# ESP8266.net
KiCad netlist of a schematic drawn in Altium Designer
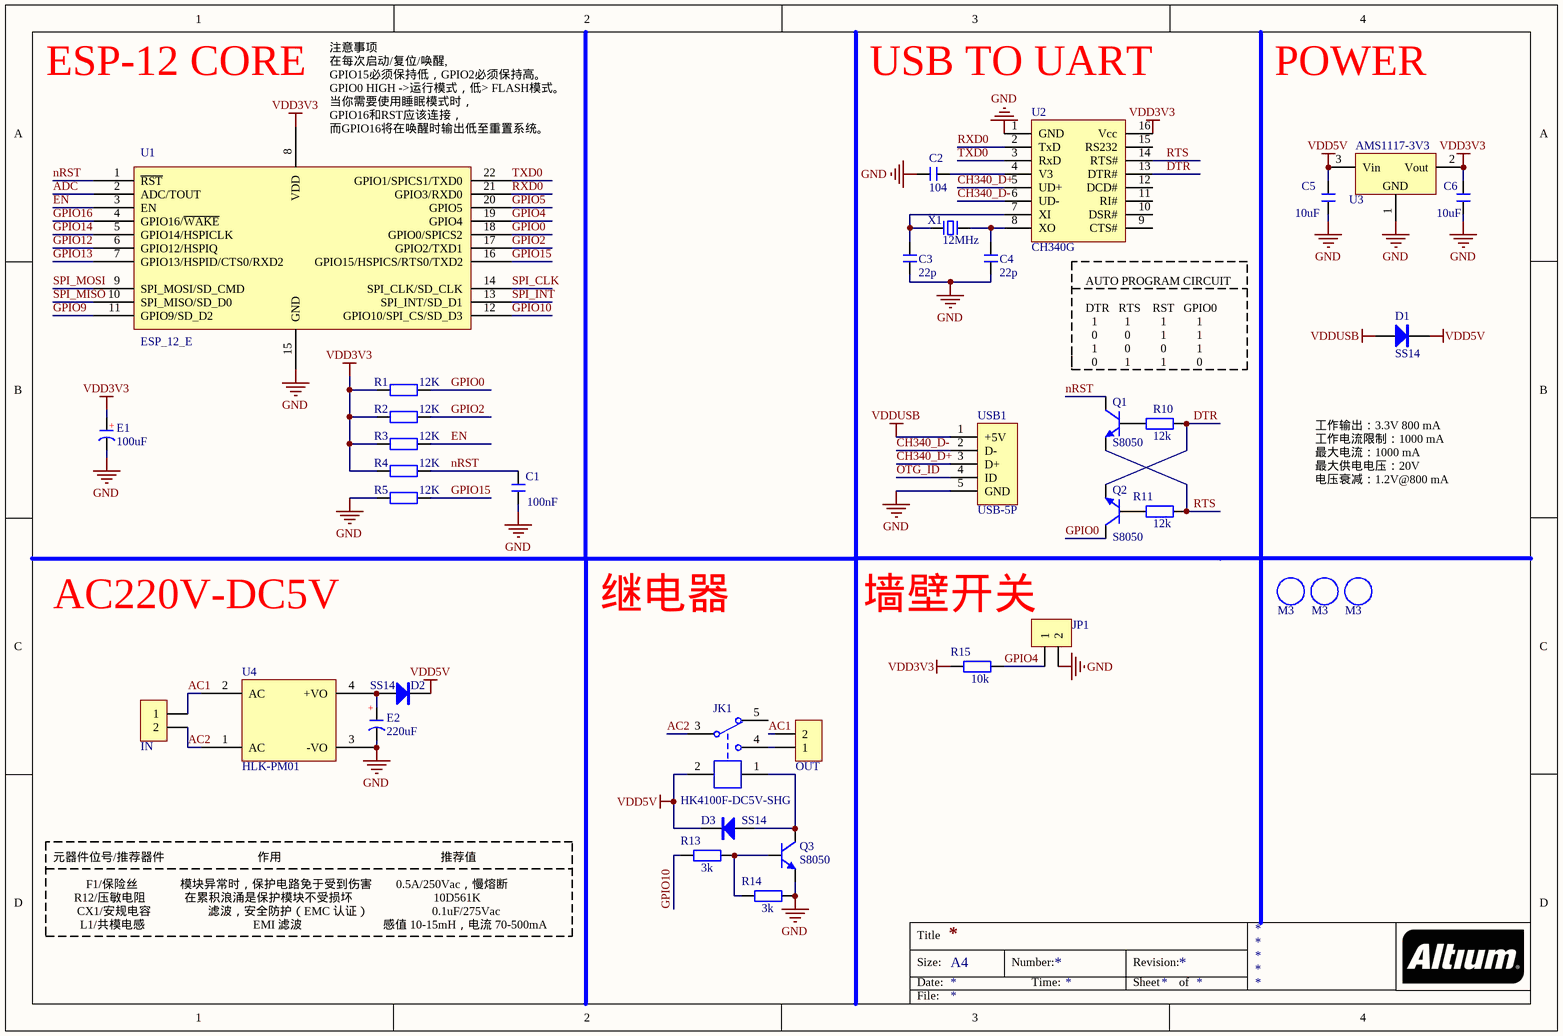
[diagram p0: ESP8266控制器.SchDoc]

(export (version "E")
  (design (tool "Eeschema 10.0.6"))
  (components
    (comp (ref "1")
      (value "M3")
      (footprint "M3 125X200")
      (description "铜柱孔")
      (fields (field (name "版权归属") "源创客"))
      (libsource (lib "海龍集成库") (part "M3"))
    )
    (comp (ref "2")
      (value "M3")
      (footprint "M3 125X200")
      (description "铜柱孔")
      (fields (field (name "版权归属") "源创客"))
      (libsource (lib "海龍集成库") (part "M3"))
    )
    (comp (ref "3")
      (value "M3")
      (footprint "M3 125X200")
      (description "铜柱孔")
      (fields (field (name "版权归属") "源创客"))
      (libsource (lib "海龍集成库") (part "M3"))
    )
    (comp (ref "C1")
      (value "100nF")
      (footprint "C 0603_M")
      (description "无极性贴片电容")
      (fields (field (name "版权归属") "源创客"))
      (libsource (lib "海龍集成库") (part "C"))
    )
    (comp (ref "C2")
      (value "104")
      (footprint "C 0603_M")
      (description "无极性贴片电容")
      (fields (field (name "版权归属") "源创客"))
      (libsource (lib "海龍集成库") (part "C"))
    )
    (comp (ref "C3")
      (value "22p")
      (footprint "C 0603_M")
      (description "无极性贴片电容")
      (fields (field (name "版权归属") "源创客"))
      (libsource (lib "海龍集成库") (part "C"))
    )
    (comp (ref "C4")
      (value "22p")
      (footprint "C 0603_M")
      (description "无极性贴片电容")
      (fields (field (name "版权归属") "源创客"))
      (libsource (lib "海龍集成库") (part "C"))
    )
    (comp (ref "C5")
      (value "10uF")
      (footprint "C 0603_M")
      (description "无极性贴片电容")
      (fields (field (name "版权归属") "源创客"))
      (libsource (lib "海龍集成库") (part "C"))
    )
    (comp (ref "C6")
      (value "10uF")
      (footprint "C 0603_M")
      (description "无极性贴片电容")
      (fields (field (name "版权归属") "源创客"))
      (libsource (lib "海龍集成库") (part "C"))
    )
    (comp (ref "D1")
      (value "SS14")
      (footprint "SMA")
      (description "肖特基二极管")
      (fields (field (name "版权归属") "源创客"))
      (libsource (lib "海龍集成库") (part "SS14"))
    )
    (comp (ref "D2")
      (value "SS14")
      (footprint "SMA")
      (description "肖特基二极管")
      (fields (field (name "版权归属") "源创客"))
      (libsource (lib "海龍集成库") (part "SS14"))
    )
    (comp (ref "D3")
      (value "SS14")
      (footprint "SMA")
      (description "肖特基二极管")
      (fields (field (name "版权归属") "源创客"))
      (libsource (lib "海龍集成库") (part "SS14"))
    )
    (comp (ref "E1")
      (value "100uF")
      (footprint "CD D(7343)")
      (description "贴片钽电容")
      (fields (field (name "版权归属") "源创客"))
      (libsource (lib "海龍集成库") (part "C-CD"))
    )
    (comp (ref "E2")
      (value "220uF")
      (footprint "CD D(7343)")
      (description "贴片钽电容")
      (fields (field (name "版权归属") "源创客"))
      (libsource (lib "") (part "C-CD_1"))
    )
    (comp (ref "IN")
      (value "HDR-1X2")
      (footprint "KF301-5.0-2P")
      (description "2P接插件")
      (fields (field (name "版权归属") "源创客"))
      (libsource (lib "") (part "Header 2 5.0_1"))
    )
    (comp (ref "JK1")
      (value "HK4100F-DC5V-SHG")
      (footprint "HK4100F")
      (description "一组转换")
      (fields (field (name "版权归属") "源创客"))
      (libsource (lib "海龍集成库") (part "HK4100F"))
    )
    (comp (ref "JP1")
      (value "HDR-1X2")
      (footprint "KF350-2P")
      (description "2P接插件")
      (fields (field (name "版权归属") "源创客"))
      (libsource (lib "海龍集成库") (part "Header 2 3.5"))
    )
    (comp (ref "OUT")
      (value "HDR-1X2")
      (footprint "KF301-5.0-2P")
      (description "2P接插件")
      (fields (field (name "版权归属") "源创客"))
      (libsource (lib "海龍集成库") (part "Header 2 5.0"))
    )
    (comp (ref "Q1")
      (value "S8050")
      (footprint "SOT23-3N")
      (description "高频放大-NPN型")
      (fields (field (name "版权归属") "源创客"))
      (libsource (lib "海龍集成库") (part "8050-SMD"))
    )
    (comp (ref "Q2")
      (value "S8050")
      (footprint "SOT23-3N")
      (description "高频放大-NPN型")
      (fields (field (name "版权归属") "源创客"))
      (libsource (lib "海龍集成库") (part "8050-SMD"))
    )
    (comp (ref "Q3")
      (value "S8050")
      (footprint "SOT23-3N")
      (description "高频放大-NPN型")
      (fields (field (name "版权归属") "源创客"))
      (libsource (lib "海龍集成库") (part "8050-SMD"))
    )
    (comp (ref "R1")
      (value "12K")
      (footprint "R 0603_M")
      (description "贴片电阻")
      (fields (field (name "版权归属") "源创客"))
      (libsource (lib "海龍集成库") (part "R"))
    )
    (comp (ref "R2")
      (value "12K")
      (footprint "R 0603_M")
      (description "贴片电阻")
      (fields (field (name "版权归属") "源创客"))
      (libsource (lib "海龍集成库") (part "R"))
    )
    (comp (ref "R3")
      (value "12K")
      (footprint "R 0603_M")
      (description "贴片电阻")
      (fields (field (name "版权归属") "源创客"))
      (libsource (lib "海龍集成库") (part "R"))
    )
    (comp (ref "R4")
      (value "12K")
      (footprint "R 0603_M")
      (description "贴片电阻")
      (fields (field (name "版权归属") "源创客"))
      (libsource (lib "海龍集成库") (part "R"))
    )
    (comp (ref "R5")
      (value "12K")
      (footprint "R 0603_M")
      (description "贴片电阻")
      (fields (field (name "版权归属") "源创客"))
      (libsource (lib "海龍集成库") (part "R"))
    )
    (comp (ref "R10")
      (value "12k")
      (footprint "R 0603_M")
      (description "贴片电阻")
      (fields (field (name "版权归属") "源创客"))
      (libsource (lib "海龍集成库") (part "R"))
    )
    (comp (ref "R11")
      (value "12k")
      (footprint "R 0603_M")
      (description "贴片电阻")
      (fields (field (name "版权归属") "源创客"))
      (libsource (lib "海龍集成库") (part "R"))
    )
    (comp (ref "R13")
      (value "3k")
      (footprint "R 0603_M")
      (description "贴片电阻")
      (fields (field (name "版权归属") "源创客"))
      (libsource (lib "海龍集成库") (part "R"))
    )
    (comp (ref "R14")
      (value "3k")
      (footprint "R 0603_M")
      (description "贴片电阻")
      (fields (field (name "版权归属") "源创客"))
      (libsource (lib "海龍集成库") (part "R"))
    )
    (comp (ref "R15")
      (value "10k")
      (footprint "R 0603_M")
      (description "贴片电阻")
      (fields (field (name "版权归属") "源创客"))
      (libsource (lib "海龍集成库") (part "R"))
    )
    (comp (ref "U1")
      (value "ESP_12_E")
      (footprint "ESP_12_E_L")
      (description "ESP-12 Wi-Fi Module by AI-Thinker")
      (libsource (lib "NODEMCU_DEVKIT_V1.0") (part "ESP_12_E"))
    )
    (comp (ref "U2")
      (value "CH340G")
      (footprint "SOP16_L")
      (description "串口转USB")
      (fields (field (name "版权归属") "源创客"))
      (libsource (lib "海龍集成库") (part "CH340G"))
    )
    (comp (ref "U3")
      (value "AMS1117-3V3")
      (footprint "SOT223_L")
      (description "三端稳压芯片")
      (fields (field (name "版权归属") "源创客"))
      (libsource (lib "海龍集成库") (part "AMS1117"))
    )
    (comp (ref "U4")
      (value "HLK-PM01")
      (footprint "HLK-PM01")
      (description "220V转5V模块")
      (libsource (lib "ESP8266控制器") (part "Component_1"))
    )
    (comp (ref "USB1")
      (value "USB-5P")
      (footprint "USB-MICRO_D")
      (description "微型USB母座")
      (fields (field (name "版权归属") "源创客"))
      (libsource (lib "海龍集成库") (part "USB-5P"))
    )
    (comp (ref "X1")
      (value "12MHz")
      (footprint "OSC HC-49S")
      (description "2脚无源脚晶振")
      (fields (field (name "版权归属") "源创客"))
      (libsource (lib "海龍集成库") (part "XTAL-2P"))
    )
  )
  (nets
    (net (code "1") (name "/AC1") (class "Default")
      (node (ref "IN") (pin "1") (pinfunction "1_1") (pintype "passive"))
      (node (ref "OUT") (pin "2") (pinfunction "2_2") (pintype "passive"))
      (node (ref "U4") (pin "2") (pinfunction "AC_2") (pintype "passive"))
    )
    (net (code "2") (name "/AC2") (class "Default")
      (node (ref "IN") (pin "2") (pinfunction "2_2") (pintype "passive"))
      (node (ref "JK1") (pin "3") (pinfunction "3_3") (pintype "passive"))
      (node (ref "U4") (pin "1") (pinfunction "AC_1") (pintype "passive"))
    )
    (net (code "3") (name "/ADC") (class "Default")
      (node (ref "U1") (pin "2") (pinfunction "ADC/TOUT_2") (pintype "passive"))
    )
    (net (code "4") (name "/CH340_D+") (class "Default")
      (node (ref "U2") (pin "5") (pinfunction "UD+_5") (pintype "passive"))
      (node (ref "USB1") (pin "3") (pinfunction "D+_3") (pintype "passive"))
    )
    (net (code "5") (name "/CH340_D-") (class "Default")
      (node (ref "U2") (pin "6") (pinfunction "UD-_6") (pintype "passive"))
      (node (ref "USB1") (pin "2") (pinfunction "D-_2") (pintype "passive"))
    )
    (net (code "6") (name "/DTR") (class "Default")
      (node (ref "Q2") (pin "2") (pinfunction "E_2") (pintype "passive"))
      (node (ref "R10") (pin "1") (pinfunction "1_1") (pintype "passive"))
      (node (ref "U2") (pin "13") (pinfunction "DTR#_13") (pintype "passive"))
    )
    (net (code "7") (name "/EN") (class "Default")
      (node (ref "R3") (pin "2") (pinfunction "2_2") (pintype "passive"))
      (node (ref "U1") (pin "3") (pinfunction "EN_3") (pintype "passive"))
    )
    (net (code "8") (name "/GPIO0") (class "Default")
      (node (ref "Q2") (pin "3") (pinfunction "C_3") (pintype "passive"))
      (node (ref "R1") (pin "2") (pinfunction "2_2") (pintype "passive"))
      (node (ref "U1") (pin "18") (pinfunction "GPIO0/SPICS2_18") (pintype "passive"))
    )
    (net (code "9") (name "/GPIO2") (class "Default")
      (node (ref "R2") (pin "2") (pinfunction "2_2") (pintype "passive"))
      (node (ref "U1") (pin "17") (pinfunction "GPIO2/TXD1_17") (pintype "passive"))
    )
    (net (code "10") (name "/GPIO4") (class "Default")
      (node (ref "JP1") (pin "1") (pinfunction "1_1") (pintype "passive"))
      (node (ref "R15") (pin "1") (pinfunction "1_1") (pintype "passive"))
      (node (ref "U1") (pin "19") (pinfunction "GPIO4_19") (pintype "passive"))
    )
    (net (code "11") (name "/GPIO5") (class "Default")
      (node (ref "U1") (pin "20") (pinfunction "GPIO5_20") (pintype "passive"))
    )
    (net (code "12") (name "/GPIO9") (class "Default")
      (node (ref "U1") (pin "11") (pinfunction "GPIO9/SD_D2_11") (pintype "passive"))
    )
    (net (code "13") (name "/GPIO10") (class "Default")
      (node (ref "R13") (pin "2") (pinfunction "2_2") (pintype "passive"))
      (node (ref "U1") (pin "12") (pinfunction "GPIO10/SPI_CS/SD_D3_12") (pintype "passive"))
    )
    (net (code "14") (name "/GPIO12") (class "Default")
      (node (ref "U1") (pin "6") (pinfunction "GPIO12/HSPIQ_6") (pintype "passive"))
    )
    (net (code "15") (name "/GPIO13") (class "Default")
      (node (ref "U1") (pin "7") (pinfunction "GPIO13/HSPID/CTS0/RXD2_7") (pintype "passive"))
    )
    (net (code "16") (name "/GPIO14") (class "Default")
      (node (ref "U1") (pin "5") (pinfunction "GPIO14/HSPICLK_5") (pintype "passive"))
    )
    (net (code "17") (name "/GPIO15") (class "Default")
      (node (ref "R5") (pin "2") (pinfunction "2_2") (pintype "passive"))
      (node (ref "U1") (pin "16") (pinfunction "GPIO15/HSPICS/RTS0/TXD2_16") (pintype "passive"))
    )
    (net (code "18") (name "/GPIO16") (class "Default")
      (node (ref "U1") (pin "4") (pinfunction "GPIO16/~{WAKE}_4") (pintype "passive"))
    )
    (net (code "19") (name "/OTG_ID") (class "Default")
      (node (ref "USB1") (pin "4") (pinfunction "ID_4") (pintype "passive"))
    )
    (net (code "20") (name "/RTS") (class "Default")
      (node (ref "Q1") (pin "2") (pinfunction "E_2") (pintype "passive"))
      (node (ref "R11") (pin "1") (pinfunction "1_1") (pintype "passive"))
      (node (ref "U2") (pin "14") (pinfunction "RTS#_14") (pintype "passive"))
    )
    (net (code "21") (name "/RXD0") (class "Default")
      (node (ref "U1") (pin "21") (pinfunction "GPIO3/RXD0_21") (pintype "passive"))
      (node (ref "U2") (pin "2") (pinfunction "TxD_2") (pintype "passive"))
    )
    (net (code "22") (name "/SPI_CLK") (class "Default")
      (node (ref "U1") (pin "14") (pinfunction "SPI_CLK/SD_CLK_14") (pintype "passive"))
    )
    (net (code "23") (name "/SPI_INT") (class "Default")
      (node (ref "U1") (pin "13") (pinfunction "SPI_INT/SD_D1_13") (pintype "passive"))
    )
    (net (code "24") (name "/SPI_MISO") (class "Default")
      (node (ref "U1") (pin "10") (pinfunction "SPI_MISO/SD_D0_10") (pintype "passive"))
    )
    (net (code "25") (name "/SPI_MOSI") (class "Default")
      (node (ref "U1") (pin "9") (pinfunction "SPI_MOSI/SD_CMD_9") (pintype "passive"))
    )
    (net (code "26") (name "/TXD0") (class "Default")
      (node (ref "U1") (pin "22") (pinfunction "GPIO1/SPICS1/TXD0_22") (pintype "passive"))
      (node (ref "U2") (pin "3") (pinfunction "RxD_3") (pintype "passive"))
    )
    (net (code "27") (name "/nRST") (class "Default")
      (node (ref "C1") (pin "2") (pinfunction "2_2") (pintype "passive"))
      (node (ref "Q1") (pin "3") (pinfunction "C_3") (pintype "passive"))
      (node (ref "R4") (pin "2") (pinfunction "2_2") (pintype "passive"))
      (node (ref "U1") (pin "1") (pinfunction "~{RST}_1") (pintype "passive"))
    )
    (net (code "28") (name "GND") (class "Default")
      (node (ref "C1") (pin "1") (pinfunction "1_1") (pintype "passive"))
      (node (ref "C2") (pin "2") (pinfunction "2_2") (pintype "passive"))
      (node (ref "C3") (pin "2") (pinfunction "2_2") (pintype "passive"))
      (node (ref "C4") (pin "2") (pinfunction "2_2") (pintype "passive"))
      (node (ref "C5") (pin "2") (pinfunction "2_2") (pintype "passive"))
      (node (ref "C6") (pin "2") (pinfunction "2_2") (pintype "passive"))
      (node (ref "E1") (pin "2") (pinfunction "K_2") (pintype "passive"))
      (node (ref "E2") (pin "2") (pinfunction "K_2") (pintype "passive"))
      (node (ref "JP1") (pin "2") (pinfunction "2_2") (pintype "passive"))
      (node (ref "Q3") (pin "2") (pinfunction "E_2") (pintype "passive"))
      (node (ref "R14") (pin "1") (pinfunction "1_1") (pintype "passive"))
      (node (ref "R5") (pin "1") (pinfunction "1_1") (pintype "passive"))
      (node (ref "U1") (pin "15") (pinfunction "GND_15") (pintype "passive"))
      (node (ref "U2") (pin "1") (pinfunction "GND_1") (pintype "passive"))
      (node (ref "U3") (pin "1") (pinfunction "GND_1") (pintype "passive"))
      (node (ref "U4") (pin "3") (pinfunction "-VO_3") (pintype "passive"))
      (node (ref "USB1") (pin "5") (pinfunction "GND_5") (pintype "passive"))
    )
    (net (code "29") (name "Net-(D2-A)") (class "Default")
      (node (ref "D2") (pin "1") (pinfunction "A_1") (pintype "passive"))
      (node (ref "E2") (pin "1") (pinfunction "A_1") (pintype "passive"))
      (node (ref "U4") (pin "4") (pinfunction "+VO_4") (pintype "passive"))
    )
    (net (code "30") (name "Net-(D3-A)") (class "Default")
      (node (ref "D3") (pin "1") (pinfunction "A_1") (pintype "passive"))
      (node (ref "JK1") (pin "1") (pinfunction "1_1") (pintype "passive"))
      (node (ref "Q3") (pin "3") (pinfunction "C_3") (pintype "passive"))
    )
    (net (code "31") (name "Net-(JK1-Pad4)") (class "Default")
      (node (ref "JK1") (pin "4") (pinfunction "4_4") (pintype "passive"))
      (node (ref "OUT") (pin "1") (pinfunction "1_1") (pintype "passive"))
    )
    (net (code "32") (name "Net-(Q1-B)") (class "Default")
      (node (ref "Q1") (pin "1") (pinfunction "B_1") (pintype "passive"))
      (node (ref "R10") (pin "2") (pinfunction "2_2") (pintype "passive"))
    )
    (net (code "33") (name "Net-(Q2-B)") (class "Default")
      (node (ref "Q2") (pin "1") (pinfunction "B_1") (pintype "passive"))
      (node (ref "R11") (pin "2") (pinfunction "2_2") (pintype "passive"))
    )
    (net (code "34") (name "Net-(Q3-B)") (class "Default")
      (node (ref "Q3") (pin "1") (pinfunction "B_1") (pintype "passive"))
      (node (ref "R13") (pin "1") (pinfunction "1_1") (pintype "passive"))
      (node (ref "R14") (pin "2") (pinfunction "2_2") (pintype "passive"))
    )
    (net (code "35") (name "Net-(U2-V3)") (class "Default")
      (node (ref "C2") (pin "1") (pinfunction "1_1") (pintype "passive"))
      (node (ref "U2") (pin "4") (pinfunction "V3_4") (pintype "passive"))
    )
    (net (code "36") (name "Net-(U2-XI)") (class "Default")
      (node (ref "C3") (pin "1") (pinfunction "1_1") (pintype "passive"))
      (node (ref "U2") (pin "7") (pinfunction "XI_7") (pintype "passive"))
      (node (ref "X1") (pin "1") (pinfunction "1_1") (pintype "passive"))
    )
    (net (code "37") (name "Net-(U2-XO)") (class "Default")
      (node (ref "C4") (pin "1") (pinfunction "1_1") (pintype "passive"))
      (node (ref "U2") (pin "8") (pinfunction "XO_8") (pintype "passive"))
      (node (ref "X1") (pin "2") (pinfunction "2_2") (pintype "passive"))
    )
    (net (code "38") (name "VDD3V3") (class "Default")
      (node (ref "C6") (pin "1") (pinfunction "1_1") (pintype "passive"))
      (node (ref "E1") (pin "1") (pinfunction "A_1") (pintype "passive"))
      (node (ref "R1") (pin "1") (pinfunction "1_1") (pintype "passive"))
      (node (ref "R15") (pin "2") (pinfunction "2_2") (pintype "passive"))
      (node (ref "R2") (pin "1") (pinfunction "1_1") (pintype "passive"))
      (node (ref "R3") (pin "1") (pinfunction "1_1") (pintype "passive"))
      (node (ref "R4") (pin "1") (pinfunction "1_1") (pintype "passive"))
      (node (ref "U1") (pin "8") (pinfunction "VDD_8") (pintype "passive"))
      (node (ref "U2") (pin "16") (pinfunction "Vcc_16") (pintype "passive"))
      (node (ref "U3") (pin "2") (pinfunction "Vout_2") (pintype "passive"))
    )
    (net (code "39") (name "VDD5V") (class "Default")
      (node (ref "C5") (pin "1") (pinfunction "1_1") (pintype "passive"))
      (node (ref "D1") (pin "2") (pinfunction "K_2") (pintype "passive"))
      (node (ref "D2") (pin "2") (pinfunction "K_2") (pintype "passive"))
      (node (ref "D3") (pin "2") (pinfunction "K_2") (pintype "passive"))
      (node (ref "JK1") (pin "2") (pinfunction "2_2") (pintype "passive"))
      (node (ref "U3") (pin "3") (pinfunction "Vin_3") (pintype "passive"))
    )
    (net (code "40") (name "VDDUSB") (class "Default")
      (node (ref "D1") (pin "1") (pinfunction "A_1") (pintype "passive"))
      (node (ref "USB1") (pin "1") (pinfunction "+5V_1") (pintype "passive"))
    )
    (net (code "41") (name "unconnected-(JK1-Pad5)") (class "Default")
      (node (ref "JK1") (pin "5") (pinfunction "5_5") (pintype "passive"))
    )
    (net (code "42") (name "unconnected-(U2-CTS#-Pad9)") (class "Default")
      (node (ref "U2") (pin "9") (pinfunction "CTS#_9") (pintype "passive"))
    )
    (net (code "43") (name "unconnected-(U2-DCD#-Pad12)") (class "Default")
      (node (ref "U2") (pin "12") (pinfunction "DCD#_12") (pintype "passive"))
    )
    (net (code "44") (name "unconnected-(U2-DSR#-Pad10)") (class "Default")
      (node (ref "U2") (pin "10") (pinfunction "DSR#_10") (pintype "passive"))
    )
    (net (code "45") (name "unconnected-(U2-RI#-Pad11)") (class "Default")
      (node (ref "U2") (pin "11") (pinfunction "RI#_11") (pintype "passive"))
    )
    (net (code "46") (name "unconnected-(U2-RS232-Pad15)") (class "Default")
      (node (ref "U2") (pin "15") (pinfunction "RS232_15") (pintype "passive"))
    )
  )
)
